# GNSS_FE_PROD.net
KiCad netlist of a schematic drawn in Altium Designer
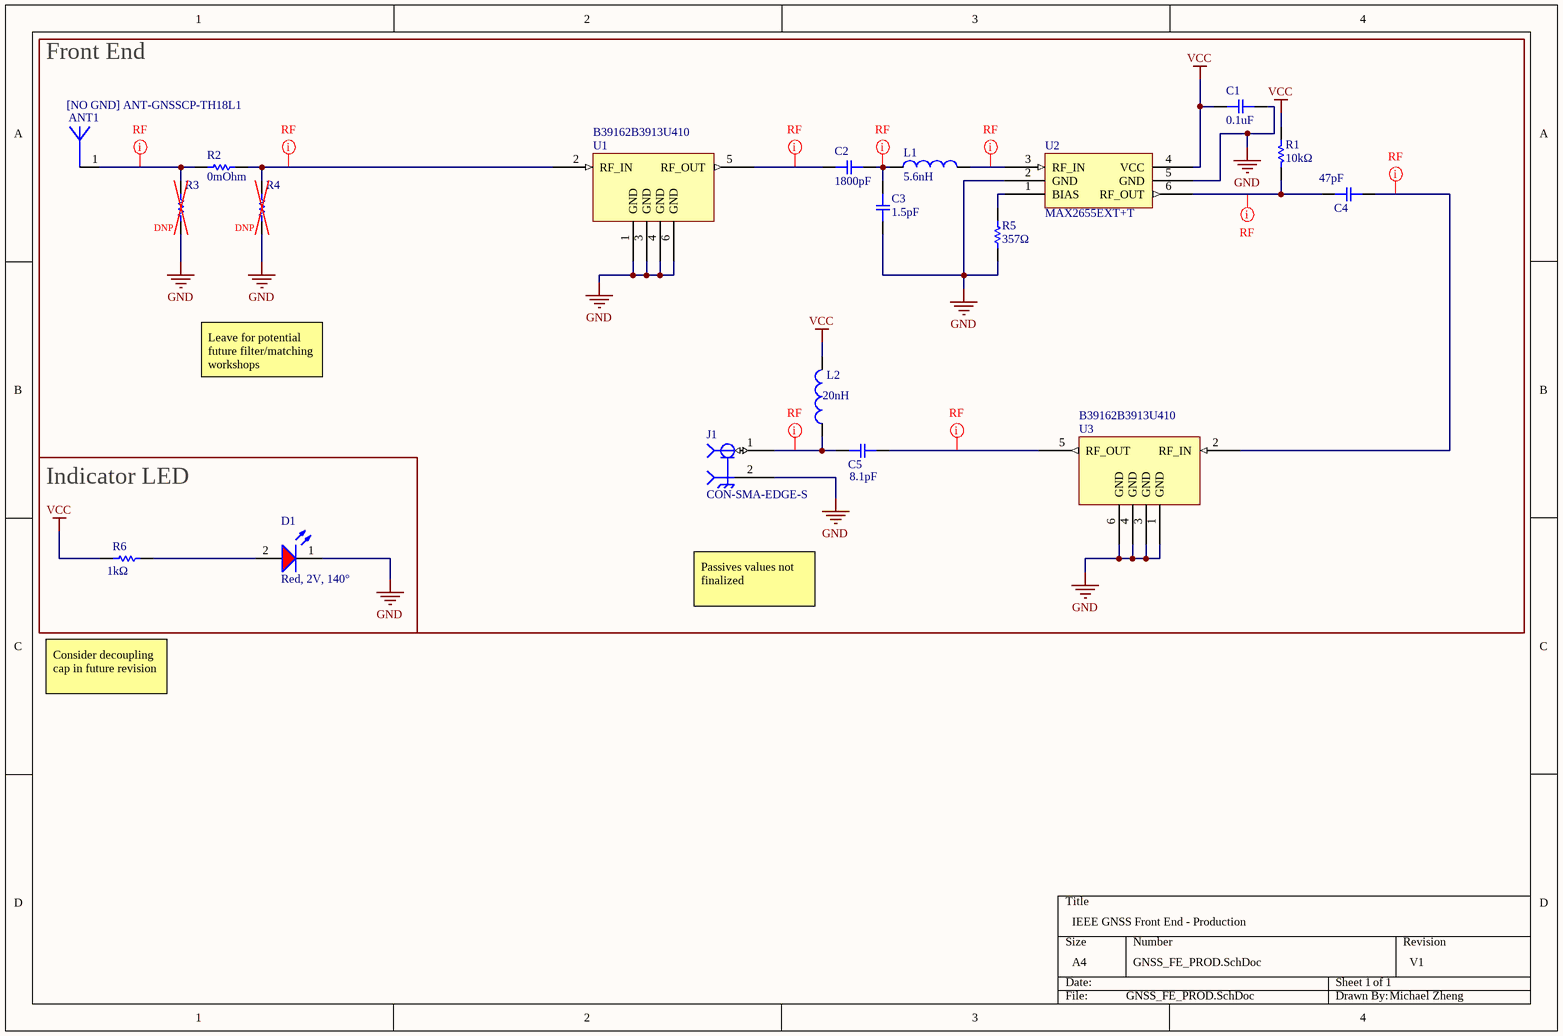
[diagram p0: GNSS_FE_PROD.SchDoc]

(export (version "E")
  (design (tool "Eeschema 10.0.6"))
  (components
    (comp (ref "ANT1")
      (value "[NO GND] ANT-GNSSCP-TH18L1")
      (footprint "[NO GND] ANT-GNSSCP-TH18L1")
      (description "CERAMIC PATCH GNSS ANTENNA")
      (libsource (lib "Symbols") (part "[NO GND] ANT-GNSSCP-TH18L1"))
    )
    (comp (ref "C1")
      (value "GCM188L81H104KA57D")
      (footprint "CAP_MURATA_0603")
      (description "CAP CER 0.1UF 50V X8L 0603")
      (fields (field (name "CAPACITANCE") "0.1uF"))
      (libsource (lib "Symbols") (part "GCM188L81H104KA57D"))
    )
    (comp (ref "C2")
      (value "GRM1555C1H182JA01D")
      (footprint "0402_CAP")
      (description "CAP CER 1800PF 50V C0G/NP0 0402")
      (fields (field (name "CAPACITANCE") "1800pF"))
      (libsource (lib "Symbols") (part "GRM1555C1H102JA01D"))
    )
    (comp (ref "C3")
      (value "GJM1555C1H1R5WB01D")
      (footprint "0402_CAP")
      (description "CAP CER 1.5PF 50V C0G/NP0 0402")
      (fields (field (name "CAPACITANCE") "1.5pF"))
      (libsource (lib "Symbols") (part "GRM1555C1H102JA01D"))
    )
    (comp (ref "C4")
      (value "GJM1555C1H470FB01D")
      (footprint "0402_CAP")
      (description "CAP CER 47PF 50V C0G/NP0 0402")
      (fields (field (name "CAPACITANCE") "47pF"))
      (libsource (lib "Symbols") (part "GRM1555C1H102JA01D"))
    )
    (comp (ref "C5")
      (value "GJM1555C1H8R1BB01D")
      (footprint "0402_CAP")
      (description "CAP CER 8.1PF 50V C0G/NP0 0402")
      (fields (field (name "CAPACITANCE") "8.1pF"))
      (libsource (lib "Symbols") (part "GRM1555C1H102JA01D"))
    )
    (comp (ref "D1")
      (value "Red, 2V, 140°")
      (footprint "WL-SMCW")
      (description "WL-SMCW Mono-color Chip LED Waterclear, SMT, size 0603, Red, 2V, 140°")
      (fields
        (field (name "MANUFACTURER PART NUMBER") "150060RS75000")
        (field (name "MANUFACTURER") "Wurth Elektronik")
      )
      (libsource (lib "Symbols") (part "150060RS75000"))
    )
    (comp (ref "J1")
      (value "CON-SMA-EDGE-S")
      (footprint "RFSOLUTIONS_CON-SMA-EDGE-S")
      (description "CONN SMA JACK STR EDGE MNT")
      (libsource (lib "Symbols") (part "CON-SMA-EDGE-S"))
    )
    (comp (ref "L1")
      (value "5.6nH")
      (footprint "INDC1006X60N")
      (description "FIXED IND 5.6NH 600MA 0.18OHM SM")
      (fields (field (name "MP") "LQW15AN3N6C10D") (field (name "Comment") "LQG15HN5N6C02D"))
      (libsource (lib "Symbols") (part "LQW15AN3N6C10D"))
    )
    (comp (ref "L2")
      (value "20nH")
      (footprint "INDC1006X60N")
      (description "FIXED IND 20NH 800MA 0.186OHM SM")
      (fields (field (name "MP") "LQW15AN3N6C10D") (field (name "Comment") "LQW15AN20NG8ZD"))
      (libsource (lib "") (part "LQW15AN3N6C10D_1"))
    )
    (comp (ref "R1")
      (value "RC0402FR-0710KL")
      (footprint "0402_CAP")
      (description "RES 10K OHM 1% 1/16W 0402")
      (fields
        (field (name "TOLERANCE") "5%")
        (field (name "RESISTANCE") "10kΩ")
        (field (name "MANUFACTURER") "Yageo")
      )
      (libsource (lib "Symbols") (part "RC0402JR-070RL"))
    )
    (comp (ref "R2")
      (value "RC0402JR-070RL")
      (footprint "0402_CAP")
      (description "RES 0 OHM JUMPER 1/16W 0402")
      (fields
        (field (name "TOLERANCE") "5%")
        (field (name "RESISTANCE") "0mOhm")
        (field (name "MANUFACTURER") "Yageo")
      )
      (libsource (lib "Symbols") (part "RC0402JR-070RL"))
    )
    (comp (ref "R3")
      (value "RC0402JR-070RL")
      (footprint "0402_CAP")
      (description "RES 0 OHM JUMPER 1/16W 0402")
      (fields (field (name "TOLERANCE") "5%") (field (name "MANUFACTURER") "Yageo"))
      (libsource (lib "Symbols") (part "RC0402JR-070RL"))
    )
    (comp (ref "R4")
      (value "RC0402JR-070RL")
      (footprint "0402_CAP")
      (description "RES 0 OHM JUMPER 1/16W 0402")
      (fields (field (name "TOLERANCE") "5%") (field (name "MANUFACTURER") "Yageo"))
      (libsource (lib "Symbols") (part "RC0402JR-070RL"))
    )
    (comp (ref "R5")
      (value "RC0402FR-07357RL")
      (footprint "RC0603JR-070RL")
      (description "RES 357 OHM 1% 1/16W 0402")
      (fields
        (field (name "TOLERANCE") "5%")
        (field (name "RESISTANCE") "357Ω")
        (field (name "MANUFACTURER") "Yageo")
      )
      (libsource (lib "Symbols") (part "RC0603JR-070RL"))
    )
    (comp (ref "R6")
      (value "RC0603FR-071KL")
      (footprint "RC0603JR-070RL")
      (description "1 kOhms ±1% 0.1W, 1/10W Chip Resistor 0603 (1608 Metric) Moisture Resistant Thick Film")
      (fields
        (field (name "TOLERANCE") "5%")
        (field (name "RESISTANCE") "1kΩ")
        (field (name "MANUFACTURER") "Yageo")
      )
      (libsource (lib "Symbols") (part "RC0603JR-070RL"))
    )
    (comp (ref "U1")
      (value "B39162B3913U410")
      (footprint "B39162B3913U410")
      (description "FILTER SAW 1.588GHZ 6SMD")
      (libsource (lib "") (part "B39162B3913U410_1"))
    )
    (comp (ref "U2")
      (value "MAX2655EXT+T")
      (footprint "MAX2655EXT+T")
      (description "IC AMP GPS 1.4GHZ-1.7GHZ SC70-6")
      (libsource (lib "Symbols") (part "MAX2655EXT+T"))
    )
    (comp (ref "U3")
      (value "B39162B3913U410")
      (footprint "B39162B3913U410")
      (description "FILTER SAW 1.588GHZ 6SMD")
      (libsource (lib "Symbols") (part "B39162B3913U410"))
    )
  )
  (nets
    (net (code "1") (name "GND") (class "Default")
      (node (ref "C1") (pin "2") (pinfunction "2_2") (pintype "passive"))
      (node (ref "C3") (pin "1") (pinfunction "1_1") (pintype "passive"))
      (node (ref "D1") (pin "1") (pinfunction "K_1") (pintype "passive"))
      (node (ref "J1") (pin "2") (pinfunction "GND_2") (pintype "power_in"))
      (node (ref "R3") (pin "1") (pinfunction "1_1") (pintype "passive"))
      (node (ref "R4") (pin "1") (pinfunction "1_1") (pintype "passive"))
      (node (ref "R5") (pin "2") (pinfunction "2_2") (pintype "passive"))
      (node (ref "U1") (pin "1") (pinfunction "GND_1") (pintype "power_in"))
      (node (ref "U1") (pin "3") (pinfunction "GND_3") (pintype "power_in"))
      (node (ref "U1") (pin "4") (pinfunction "GND_4") (pintype "power_in"))
      (node (ref "U1") (pin "6") (pinfunction "GND_6") (pintype "power_in"))
      (node (ref "U2") (pin "2") (pinfunction "GND_2") (pintype "power_in"))
      (node (ref "U2") (pin "5") (pinfunction "GND_5") (pintype "power_in"))
      (node (ref "U3") (pin "1") (pinfunction "GND_1") (pintype "power_in"))
      (node (ref "U3") (pin "3") (pinfunction "GND_3") (pintype "power_in"))
      (node (ref "U3") (pin "4") (pinfunction "GND_4") (pintype "power_in"))
      (node (ref "U3") (pin "6") (pinfunction "GND_6") (pintype "power_in"))
    )
    (net (code "2") (name "Net-(ANT1-RF_IN)") (class "Default")
      (node (ref "ANT1") (pin "1") (pinfunction "RF_IN_1") (pintype "passive"))
      (node (ref "R2") (pin "2") (pinfunction "2_2") (pintype "passive"))
      (node (ref "R3") (pin "2") (pinfunction "2_2") (pintype "passive"))
    )
    (net (code "3") (name "Net-(C2-Pad2)") (class "Default")
      (node (ref "C2") (pin "2") (pinfunction "2_2") (pintype "passive"))
      (node (ref "C3") (pin "2") (pinfunction "2_2") (pintype "passive"))
      (node (ref "L1") (pin "2") (pinfunction "2_2") (pintype "passive"))
    )
    (net (code "4") (name "Net-(D1-A)") (class "Default")
      (node (ref "D1") (pin "2") (pinfunction "A_2") (pintype "passive"))
      (node (ref "R6") (pin "2") (pinfunction "2_2") (pintype "passive"))
    )
    (net (code "5") (name "Net-(J1-RF)") (class "Default")
      (node (ref "C5") (pin "2") (pinfunction "2_2") (pintype "passive"))
      (node (ref "J1") (pin "1") (pinfunction "RF_1") (pintype "bidirectional"))
      (node (ref "L2") (pin "1") (pinfunction "1_1") (pintype "passive"))
    )
    (net (code "6") (name "Net-(U1-RF_IN)") (class "Default")
      (node (ref "R2") (pin "1") (pinfunction "1_1") (pintype "passive"))
      (node (ref "R4") (pin "2") (pinfunction "2_2") (pintype "passive"))
      (node (ref "U1") (pin "2") (pinfunction "RF_IN_2") (pintype "input"))
    )
    (net (code "7") (name "Net-(U1-RF_OUT)") (class "Default")
      (node (ref "C2") (pin "1") (pinfunction "1_1") (pintype "passive"))
      (node (ref "U1") (pin "5") (pinfunction "RF_OUT_5") (pintype "output"))
    )
    (net (code "8") (name "Net-(U2-BIAS)") (class "Default")
      (node (ref "R5") (pin "1") (pinfunction "1_1") (pintype "passive"))
      (node (ref "U2") (pin "1") (pinfunction "BIAS_1") (pintype "passive"))
    )
    (net (code "9") (name "Net-(U2-RF_IN)") (class "Default")
      (node (ref "L1") (pin "1") (pinfunction "1_1") (pintype "passive"))
      (node (ref "U2") (pin "3") (pinfunction "RF_IN_3") (pintype "input"))
    )
    (net (code "10") (name "Net-(U2-RF_OUT)") (class "Default")
      (node (ref "C4") (pin "1") (pinfunction "1_1") (pintype "passive"))
      (node (ref "R1") (pin "2") (pinfunction "2_2") (pintype "passive"))
      (node (ref "U2") (pin "6") (pinfunction "RF_OUT_6") (pintype "output"))
    )
    (net (code "11") (name "Net-(U3-RF_IN)") (class "Default")
      (node (ref "C4") (pin "2") (pinfunction "2_2") (pintype "passive"))
      (node (ref "U3") (pin "2") (pinfunction "RF_IN_2") (pintype "input"))
    )
    (net (code "12") (name "Net-(U3-RF_OUT)") (class "Default")
      (node (ref "C5") (pin "1") (pinfunction "1_1") (pintype "passive"))
      (node (ref "U3") (pin "5") (pinfunction "RF_OUT_5") (pintype "output"))
    )
    (net (code "13") (name "VCC") (class "Default")
      (node (ref "C1") (pin "1") (pinfunction "1_1") (pintype "passive"))
      (node (ref "L2") (pin "2") (pinfunction "2_2") (pintype "passive"))
      (node (ref "R1") (pin "1") (pinfunction "1_1") (pintype "passive"))
      (node (ref "R6") (pin "1") (pinfunction "1_1") (pintype "passive"))
      (node (ref "U2") (pin "4") (pinfunction "VCC_4") (pintype "power_in"))
    )
  )
)
